# Mercator_FeatherWing_RevA.net
KiCad netlist of a schematic drawn in EAGLE
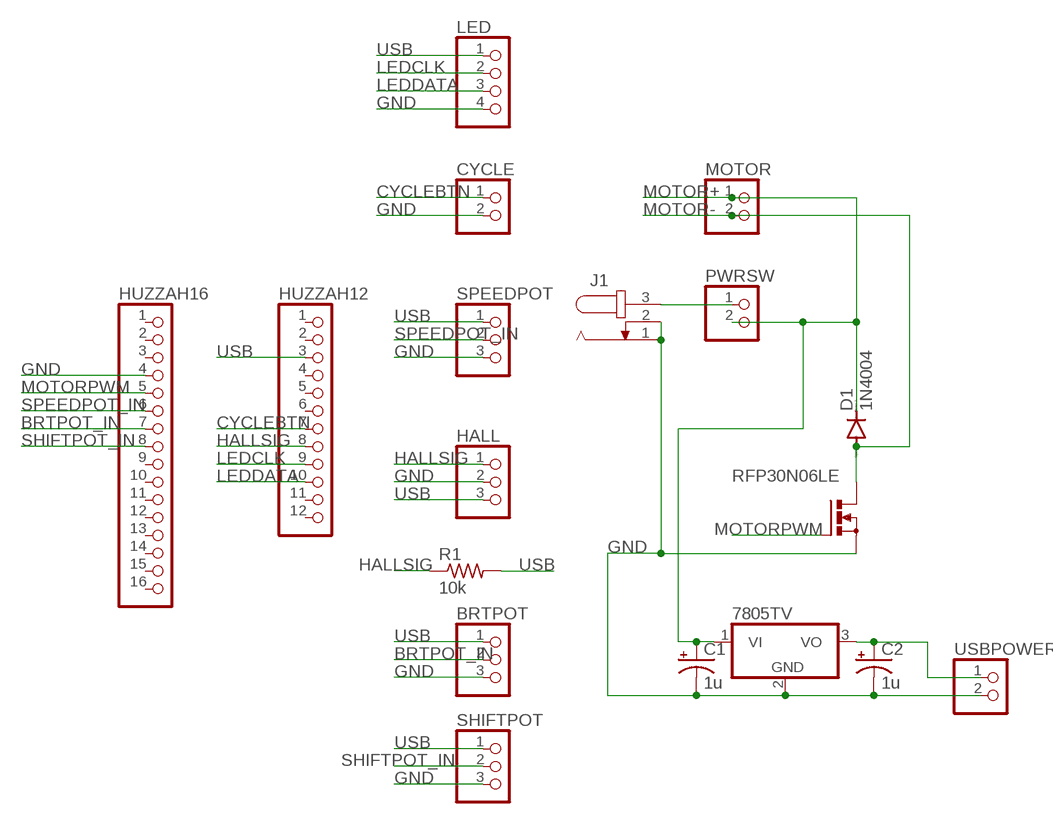
[diagram p0: schematic, sheet 1]

(export (version "E")
  (design (tool "Eeschema 10.0.6"))
  (components
    (comp (ref "7805ABV")
      (value "7805TV")
      (footprint "eagle-import:TO220V")
      (libsource (lib "eagle-import") (part "78TV05"))
    )
    (comp (ref "BRTPOT")
      (value "PINHD-1X3")
      (footprint "eagle-import:1X03")
      (libsource (lib "eagle-import") (part "PINHD-1X3"))
    )
    (comp (ref "C1")
      (value "1u")
      (footprint "eagle-import:E2-5")
      (libsource (lib "eagle-import") (part "CPOL-USE2-5"))
    )
    (comp (ref "C2")
      (value "1u")
      (footprint "eagle-import:E2-5")
      (libsource (lib "eagle-import") (part "CPOL-USE2-5"))
    )
    (comp (ref "CYCLE")
      (value "PINHD-1X2")
      (footprint "eagle-import:1X02")
      (libsource (lib "eagle-import") (part "PINHD-1X2"))
    )
    (comp (ref "D1")
      (value "1N4004")
      (footprint "eagle-import:DO41-10")
      (libsource (lib "eagle-import") (part "1N4004"))
    )
    (comp (ref "HALL")
      (value "PINHD-1X3")
      (footprint "eagle-import:1X03")
      (libsource (lib "eagle-import") (part "PINHD-1X3"))
    )
    (comp (ref "HUZZAH12")
      (value "PINHD-1X12")
      (footprint "eagle-import:1X12")
      (libsource (lib "eagle-import") (part "PINHD-1X12"))
    )
    (comp (ref "HUZZAH16")
      (value "PINHD-1X16")
      (footprint "eagle-import:1X16")
      (libsource (lib "eagle-import") (part "PINHD-1X16"))
    )
    (comp (ref "J1")
      (value "JACK-PLUG0")
      (footprint "eagle-import:SPC4077")
      (libsource (lib "eagle-import") (part "JACK-PLUG0"))
    )
    (comp (ref "LED")
      (value "PINHD-1X4")
      (footprint "eagle-import:1X04")
      (libsource (lib "eagle-import") (part "PINHD-1X4"))
    )
    (comp (ref "MOTOR")
      (value "PINHD-1X2")
      (footprint "eagle-import:1X02")
      (libsource (lib "eagle-import") (part "PINHD-1X2"))
    )
    (comp (ref "PWRSW")
      (value "PINHD-1X2")
      (footprint "eagle-import:1X02")
      (libsource (lib "eagle-import") (part "PINHD-1X2"))
    )
    (comp (ref "R1")
      (value "10k")
      (footprint "eagle-import:0207_10")
      (libsource (lib "eagle-import") (part "R-US_0207/10"))
    )
    (comp (ref "RFP30N06LE")
      (value "PMOSFET_NTO220BV")
      (footprint "eagle-import:TO220BV")
      (libsource (lib "eagle-import") (part "PMOSFET_NTO220BV"))
    )
    (comp (ref "SHIFTPOT")
      (value "PINHD-1X3")
      (footprint "eagle-import:1X03")
      (libsource (lib "eagle-import") (part "PINHD-1X3"))
    )
    (comp (ref "SPEEDPOT")
      (value "PINHD-1X3")
      (footprint "eagle-import:1X03")
      (libsource (lib "eagle-import") (part "PINHD-1X3"))
    )
    (comp (ref "USBPOWER")
      (value "PINHD-1X2")
      (footprint "eagle-import:1X02")
      (libsource (lib "eagle-import") (part "PINHD-1X2"))
    )
  )
  (nets
    (net (code "1") (name "/BRTPOT_IN") (class "Default")
      (node (ref "BRTPOT") (pin "2") (pinfunction "2_2") (pintype "passive"))
      (node (ref "HUZZAH16") (pin "7") (pinfunction "7_7") (pintype "passive"))
    )
    (net (code "2") (name "/CYCLEBTN") (class "Default")
      (node (ref "CYCLE") (pin "1") (pinfunction "1_1") (pintype "passive"))
      (node (ref "HUZZAH12") (pin "7") (pinfunction "7_7") (pintype "passive"))
    )
    (net (code "3") (name "/GND") (class "Default")
      (node (ref "7805ABV") (pin "2") (pinfunction "GND_2") (pintype "passive"))
      (node (ref "BRTPOT") (pin "3") (pinfunction "3_3") (pintype "passive"))
      (node (ref "C1") (pin "-") (pinfunction "-_-") (pintype "passive"))
      (node (ref "C2") (pin "-") (pinfunction "-_-") (pintype "passive"))
      (node (ref "CYCLE") (pin "2") (pinfunction "2_2") (pintype "passive"))
      (node (ref "HALL") (pin "2") (pinfunction "2_2") (pintype "passive"))
      (node (ref "HUZZAH16") (pin "4") (pinfunction "4_4") (pintype "passive"))
      (node (ref "J1") (pin "1") (pinfunction "1_1") (pintype "passive"))
      (node (ref "J1") (pin "2") (pinfunction "2_2") (pintype "passive"))
      (node (ref "LED") (pin "4") (pinfunction "4_4") (pintype "passive"))
      (node (ref "RFP30N06LE") (pin "S") (pinfunction "S_S") (pintype "passive"))
      (node (ref "SHIFTPOT") (pin "3") (pinfunction "3_3") (pintype "passive"))
      (node (ref "SPEEDPOT") (pin "3") (pinfunction "3_3") (pintype "passive"))
      (node (ref "USBPOWER") (pin "2") (pinfunction "2_2") (pintype "passive"))
    )
    (net (code "4") (name "/HALLSIG") (class "Default")
      (node (ref "HALL") (pin "1") (pinfunction "1_1") (pintype "passive"))
      (node (ref "HUZZAH12") (pin "8") (pinfunction "8_8") (pintype "passive"))
      (node (ref "R1") (pin "1") (pinfunction "1_1") (pintype "passive"))
    )
    (net (code "5") (name "/LEDCLK") (class "Default")
      (node (ref "HUZZAH12") (pin "9") (pinfunction "9_9") (pintype "passive"))
      (node (ref "LED") (pin "2") (pinfunction "2_2") (pintype "passive"))
    )
    (net (code "6") (name "/LEDDATA") (class "Default")
      (node (ref "HUZZAH12") (pin "10") (pinfunction "10_10") (pintype "passive"))
      (node (ref "LED") (pin "3") (pinfunction "3_3") (pintype "passive"))
    )
    (net (code "7") (name "/MOTOR+") (class "Default")
      (node (ref "7805ABV") (pin "1") (pinfunction "VI_1") (pintype "input"))
      (node (ref "C1") (pin "+") (pinfunction "+_+") (pintype "passive"))
      (node (ref "D1") (pin "C") (pinfunction "C_C") (pintype "passive"))
      (node (ref "MOTOR") (pin "1") (pinfunction "1_1") (pintype "passive"))
      (node (ref "PWRSW") (pin "2") (pinfunction "2_2") (pintype "passive"))
    )
    (net (code "8") (name "/MOTOR-") (class "Default")
      (node (ref "D1") (pin "A") (pinfunction "A_A") (pintype "passive"))
      (node (ref "MOTOR") (pin "2") (pinfunction "2_2") (pintype "passive"))
      (node (ref "RFP30N06LE") (pin "D") (pinfunction "D_D") (pintype "passive"))
    )
    (net (code "9") (name "/MOTORPWM") (class "Default")
      (node (ref "HUZZAH16") (pin "5") (pinfunction "5_5") (pintype "passive"))
      (node (ref "RFP30N06LE") (pin "G") (pinfunction "G_G") (pintype "passive"))
    )
    (net (code "10") (name "/SHIFTPOT_IN") (class "Default")
      (node (ref "HUZZAH16") (pin "8") (pinfunction "8_8") (pintype "passive"))
      (node (ref "SHIFTPOT") (pin "2") (pinfunction "2_2") (pintype "passive"))
    )
    (net (code "11") (name "/SPEEDPOT_IN") (class "Default")
      (node (ref "HUZZAH16") (pin "6") (pinfunction "6_6") (pintype "passive"))
      (node (ref "SPEEDPOT") (pin "2") (pinfunction "2_2") (pintype "passive"))
    )
    (net (code "12") (name "/USB") (class "Default")
      (node (ref "BRTPOT") (pin "1") (pinfunction "1_1") (pintype "passive"))
      (node (ref "HALL") (pin "3") (pinfunction "3_3") (pintype "passive"))
      (node (ref "HUZZAH12") (pin "3") (pinfunction "3_3") (pintype "passive"))
      (node (ref "LED") (pin "1") (pinfunction "1_1") (pintype "passive"))
      (node (ref "R1") (pin "2") (pinfunction "2_2") (pintype "passive"))
      (node (ref "SHIFTPOT") (pin "1") (pinfunction "1_1") (pintype "passive"))
      (node (ref "SPEEDPOT") (pin "1") (pinfunction "1_1") (pintype "passive"))
    )
    (net (code "13") (name "Net-(7805ABV-VO)") (class "Default")
      (node (ref "7805ABV") (pin "3") (pinfunction "VO_3") (pintype "passive"))
      (node (ref "C2") (pin "+") (pinfunction "+_+") (pintype "passive"))
      (node (ref "USBPOWER") (pin "1") (pinfunction "1_1") (pintype "passive"))
    )
    (net (code "14") (name "Net-(J1-Pad3)") (class "Default")
      (node (ref "J1") (pin "3") (pinfunction "3_3") (pintype "passive"))
      (node (ref "PWRSW") (pin "1") (pinfunction "1_1") (pintype "passive"))
    )
    (net (code "15") (name "unconnected-(HUZZAH12-Pad1)") (class "Default")
      (node (ref "HUZZAH12") (pin "1") (pinfunction "1_1") (pintype "passive"))
    )
    (net (code "16") (name "unconnected-(HUZZAH12-Pad2)") (class "Default")
      (node (ref "HUZZAH12") (pin "2") (pinfunction "2_2") (pintype "passive"))
    )
    (net (code "17") (name "unconnected-(HUZZAH12-Pad4)") (class "Default")
      (node (ref "HUZZAH12") (pin "4") (pinfunction "4_4") (pintype "passive"))
    )
    (net (code "18") (name "unconnected-(HUZZAH12-Pad5)") (class "Default")
      (node (ref "HUZZAH12") (pin "5") (pinfunction "5_5") (pintype "passive"))
    )
    (net (code "19") (name "unconnected-(HUZZAH12-Pad6)") (class "Default")
      (node (ref "HUZZAH12") (pin "6") (pinfunction "6_6") (pintype "passive"))
    )
    (net (code "20") (name "unconnected-(HUZZAH12-Pad11)") (class "Default")
      (node (ref "HUZZAH12") (pin "11") (pinfunction "11_11") (pintype "passive"))
    )
    (net (code "21") (name "unconnected-(HUZZAH12-Pad12)") (class "Default")
      (node (ref "HUZZAH12") (pin "12") (pinfunction "12_12") (pintype "passive"))
    )
    (net (code "22") (name "unconnected-(HUZZAH16-Pad1)") (class "Default")
      (node (ref "HUZZAH16") (pin "1") (pinfunction "1_1") (pintype "passive"))
    )
    (net (code "23") (name "unconnected-(HUZZAH16-Pad2)") (class "Default")
      (node (ref "HUZZAH16") (pin "2") (pinfunction "2_2") (pintype "passive"))
    )
    (net (code "24") (name "unconnected-(HUZZAH16-Pad3)") (class "Default")
      (node (ref "HUZZAH16") (pin "3") (pinfunction "3_3") (pintype "passive"))
    )
    (net (code "25") (name "unconnected-(HUZZAH16-Pad9)") (class "Default")
      (node (ref "HUZZAH16") (pin "9") (pinfunction "9_9") (pintype "passive"))
    )
    (net (code "26") (name "unconnected-(HUZZAH16-Pad10)") (class "Default")
      (node (ref "HUZZAH16") (pin "10") (pinfunction "10_10") (pintype "passive"))
    )
    (net (code "27") (name "unconnected-(HUZZAH16-Pad11)") (class "Default")
      (node (ref "HUZZAH16") (pin "11") (pinfunction "11_11") (pintype "passive"))
    )
    (net (code "28") (name "unconnected-(HUZZAH16-Pad12)") (class "Default")
      (node (ref "HUZZAH16") (pin "12") (pinfunction "12_12") (pintype "passive"))
    )
    (net (code "29") (name "unconnected-(HUZZAH16-Pad13)") (class "Default")
      (node (ref "HUZZAH16") (pin "13") (pinfunction "13_13") (pintype "passive"))
    )
    (net (code "30") (name "unconnected-(HUZZAH16-Pad14)") (class "Default")
      (node (ref "HUZZAH16") (pin "14") (pinfunction "14_14") (pintype "passive"))
    )
    (net (code "31") (name "unconnected-(HUZZAH16-Pad15)") (class "Default")
      (node (ref "HUZZAH16") (pin "15") (pinfunction "15_15") (pintype "passive"))
    )
    (net (code "32") (name "unconnected-(HUZZAH16-Pad16)") (class "Default")
      (node (ref "HUZZAH16") (pin "16") (pinfunction "16_16") (pintype "passive"))
    )
  )
)
